# UnoMuxShieldV1_0.net
KiCad netlist of a schematic drawn in EAGLE
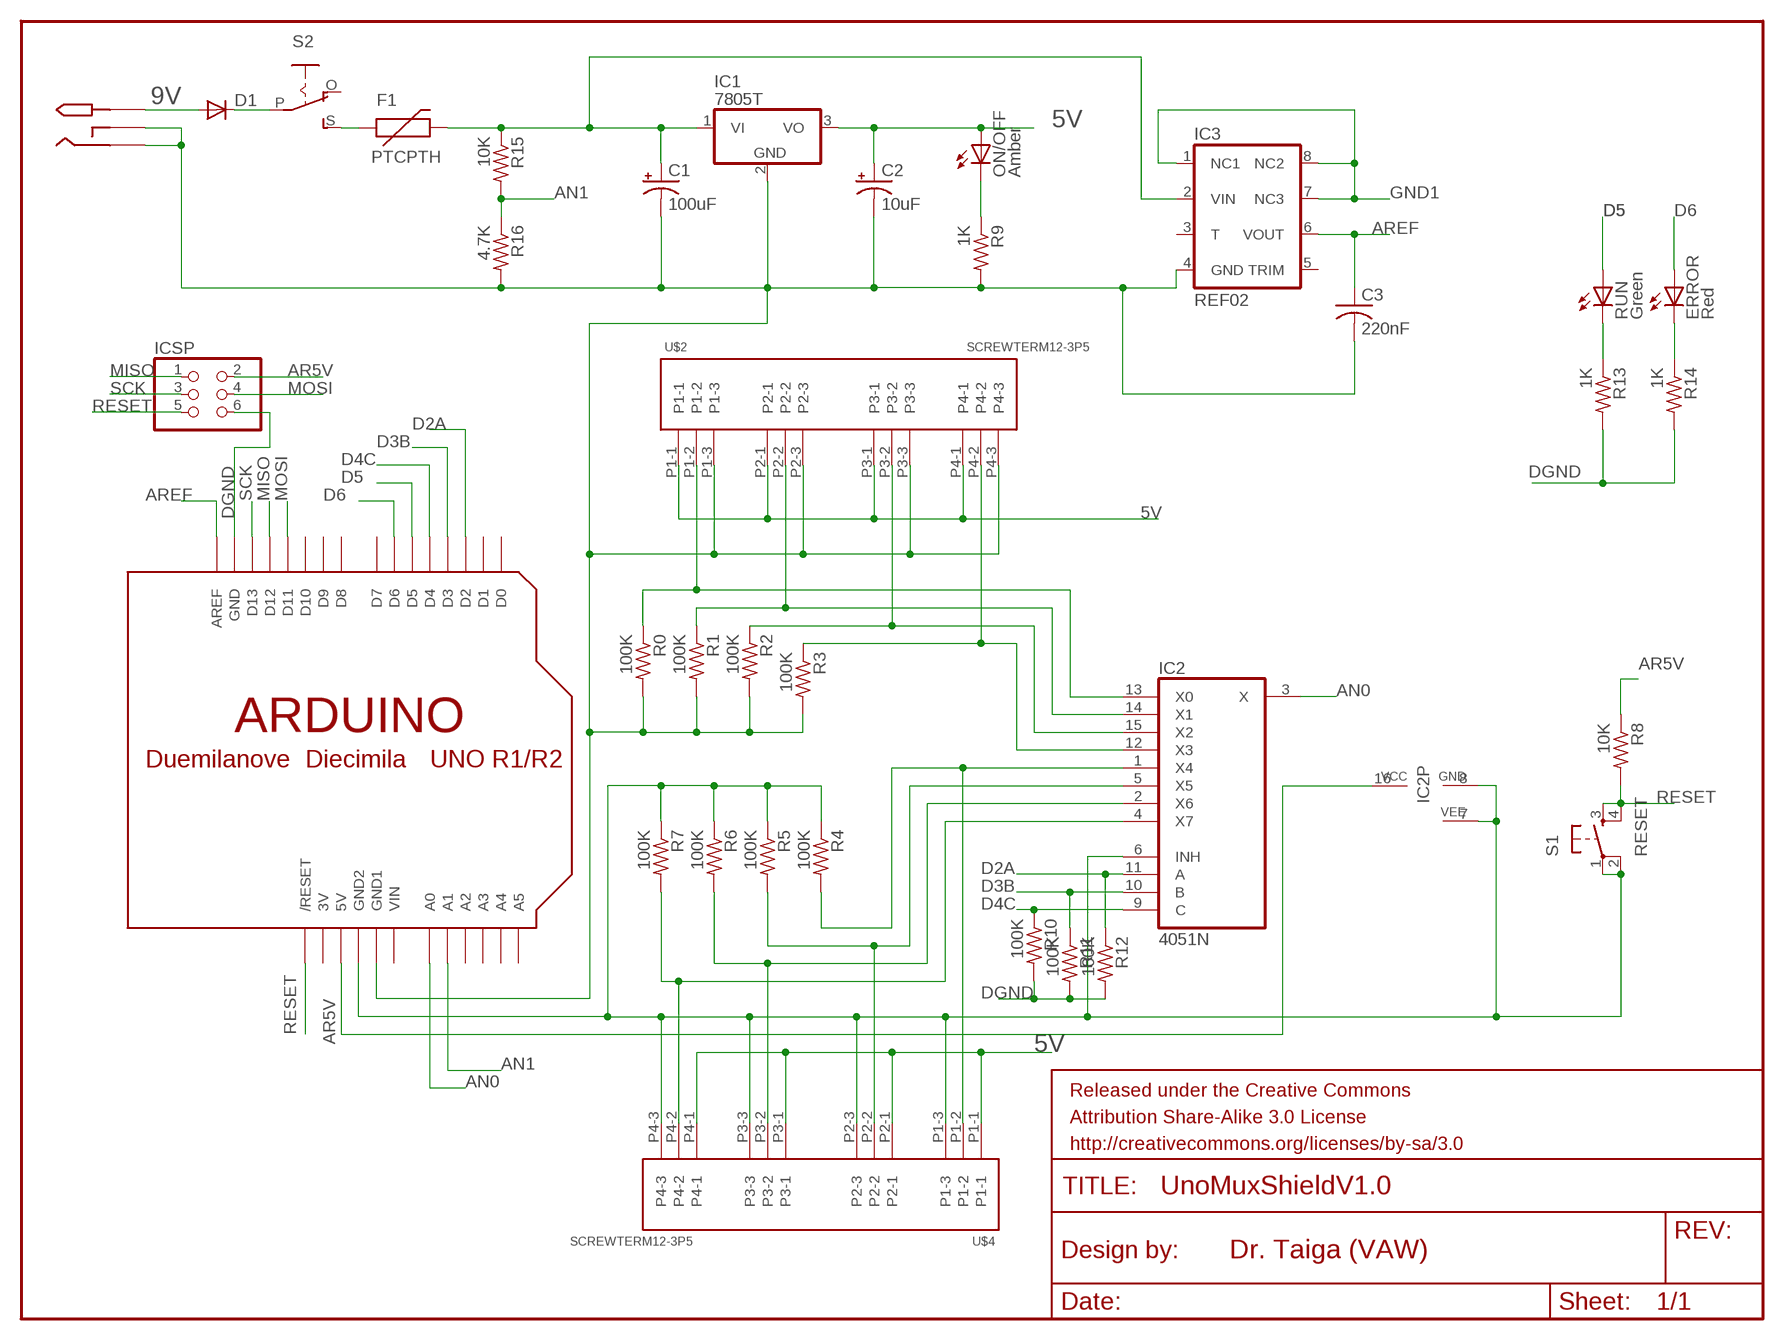
[diagram p0: schematic, sheet 1]

(export (version "E")
  (design (tool "Eeschema 10.0.6"))
  (components
    (comp (ref "C1")
      (value "100uF")
      (footprint "eagle-import:E2,5-6E")
      (libsource (lib "eagle-import") (part "CPOL-USE2,5-6E"))
    )
    (comp (ref "C2")
      (value "10uF")
      (footprint "eagle-import:E1,8-4")
      (libsource (lib "eagle-import") (part "CPOL-USE1.8-4"))
    )
    (comp (ref "C3")
      (value "220nF")
      (footprint "eagle-import:C050-024X044")
      (libsource (lib "eagle-import") (part "C-US050-024X044"))
    )
    (comp (ref "D1")
      (value "DIODEPTH")
      (footprint "eagle-import:DIODE-1N4001")
      (libsource (lib "eagle-import") (part "DIODEPTH"))
    )
    (comp (ref "ERROR")
      (value "Red")
      (footprint "eagle-import:LED3MM")
      (libsource (lib "eagle-import") (part "LED3MM"))
    )
    (comp (ref "F1")
      (value "PTCPTH")
      (footprint "eagle-import:PTC")
      (libsource (lib "eagle-import") (part "PTCPTH"))
    )
    (comp (ref "IC1")
      (value "7805T")
      (footprint "eagle-import:TO220H")
      (libsource (lib "eagle-import") (part "78T05"))
    )
    (comp (ref "IC2")
      (value "4051N")
      (footprint "eagle-import:DIL16")
      (libsource (lib "eagle-import") (part "4051N"))
    )
    (comp (ref "IC3")
      (value "REF02")
      (footprint "eagle-import:DIL08")
      (libsource (lib "eagle-import") (part "REF02"))
    )
    (comp (ref "ICSP")
      (value "PINHD-2X3")
      (footprint "eagle-import:2X03")
      (libsource (lib "eagle-import") (part "PINHD-2X3"))
    )
    (comp (ref "ON/OFF")
      (value "Amber")
      (footprint "eagle-import:LED3MM")
      (libsource (lib "eagle-import") (part "LED3MM"))
    )
    (comp (ref "R0")
      (value "100K")
      (footprint "eagle-import:0207_10")
      (libsource (lib "eagle-import") (part "R-US_0207/10"))
    )
    (comp (ref "R1")
      (value "100K")
      (footprint "eagle-import:0207_10")
      (libsource (lib "eagle-import") (part "R-US_0207/10"))
    )
    (comp (ref "R2")
      (value "100K")
      (footprint "eagle-import:0207_10")
      (libsource (lib "eagle-import") (part "R-US_0207/10"))
    )
    (comp (ref "R3")
      (value "100K")
      (footprint "eagle-import:0207_10")
      (libsource (lib "eagle-import") (part "R-US_0207/10"))
    )
    (comp (ref "R4")
      (value "100K")
      (footprint "eagle-import:0207_10")
      (libsource (lib "eagle-import") (part "R-US_0207/10"))
    )
    (comp (ref "R5")
      (value "100K")
      (footprint "eagle-import:0207_10")
      (libsource (lib "eagle-import") (part "R-US_0207/10"))
    )
    (comp (ref "R6")
      (value "100K")
      (footprint "eagle-import:0207_10")
      (libsource (lib "eagle-import") (part "R-US_0207/10"))
    )
    (comp (ref "R7")
      (value "100K")
      (footprint "eagle-import:0207_10")
      (libsource (lib "eagle-import") (part "R-US_0207/10"))
    )
    (comp (ref "R8")
      (value "10K")
      (footprint "eagle-import:0207_10")
      (libsource (lib "eagle-import") (part "R-US_0207/10"))
    )
    (comp (ref "R9")
      (value "1K")
      (footprint "eagle-import:0207_10")
      (libsource (lib "eagle-import") (part "R-US_0207/10"))
    )
    (comp (ref "R10")
      (value "100K")
      (footprint "eagle-import:0207_10")
      (libsource (lib "eagle-import") (part "R-US_0207/10"))
    )
    (comp (ref "R11")
      (value "100K")
      (footprint "eagle-import:0207_10")
      (libsource (lib "eagle-import") (part "R-US_0207/10"))
    )
    (comp (ref "R12")
      (value "100K")
      (footprint "eagle-import:0207_10")
      (libsource (lib "eagle-import") (part "R-US_0207/10"))
    )
    (comp (ref "R13")
      (value "1K")
      (footprint "eagle-import:0207_10")
      (libsource (lib "eagle-import") (part "R-US_0207/10"))
    )
    (comp (ref "R14")
      (value "1K")
      (footprint "eagle-import:0207_10")
      (libsource (lib "eagle-import") (part "R-US_0207/10"))
    )
    (comp (ref "R15")
      (value "10K")
      (footprint "eagle-import:0207_10")
      (libsource (lib "eagle-import") (part "R-US_0207/10"))
    )
    (comp (ref "R16")
      (value "4.7K")
      (footprint "eagle-import:0207_10")
      (libsource (lib "eagle-import") (part "R-US_0207/10"))
    )
    (comp (ref "RUN")
      (value "Green")
      (footprint "eagle-import:LED3MM")
      (libsource (lib "eagle-import") (part "LED3MM"))
    )
    (comp (ref "S1")
      (value "RESET")
      (footprint "eagle-import:TACTILE-PTH")
      (libsource (lib "eagle-import") (part "TAC_SWITCHPTH"))
    )
    (comp (ref "S2")
      (value "EG1218S")
      (footprint "eagle-import:EG1218")
      (libsource (lib "eagle-import") (part "EG1218S"))
    )
    (comp (ref "U$1")
      (value "ARDUINO-NOHOLE")
      (footprint "eagle-import:ARDUINO-NOHOLE")
      (libsource (lib "eagle-import") (part "ARDUINO-NOHOLE"))
    )
    (comp (ref "U$2")
      (value "SCREWTERM12-3P5")
      (footprint "eagle-import:SCREWTERM3P5")
      (libsource (lib "eagle-import") (part "SCREWTERM12-3P5"))
    )
    (comp (ref "U$4")
      (value "SCREWTERM12-3P5")
      (footprint "eagle-import:SCREWTERM3P5")
      (libsource (lib "eagle-import") (part "SCREWTERM12-3P5"))
    )
    (comp (ref "U$5")
      (value "PJ-102-A")
      (footprint "eagle-import:PJ-102-A")
      (libsource (lib "eagle-import") (part "PJ-102-A"))
    )
  )
  (nets
    (net (code "1") (name "/3V") (class "Default")
      (node (ref "U$1") (pin "3V") (pinfunction "3V_3V") (pintype "power_in"))
    )
    (net (code "2") (name "/5V") (class "Default")
      (node (ref "C2") (pin "+") (pinfunction "+_+") (pintype "passive"))
      (node (ref "IC1") (pin "3") (pinfunction "VO_3") (pintype "passive"))
      (node (ref "ON/OFF") (pin "A") (pinfunction "A_A") (pintype "passive"))
      (node (ref "U$2") (pin "P1-1") (pinfunction "P1-1_P1-1") (pintype "bidirectional"))
      (node (ref "U$2") (pin "P2-1") (pinfunction "P2-1_P2-1") (pintype "bidirectional"))
      (node (ref "U$2") (pin "P3-1") (pinfunction "P3-1_P3-1") (pintype "bidirectional"))
      (node (ref "U$2") (pin "P4-1") (pinfunction "P4-1_P4-1") (pintype "bidirectional"))
      (node (ref "U$4") (pin "P1-1") (pinfunction "P1-1_P1-1") (pintype "bidirectional"))
      (node (ref "U$4") (pin "P2-1") (pinfunction "P2-1_P2-1") (pintype "bidirectional"))
      (node (ref "U$4") (pin "P3-1") (pinfunction "P3-1_P3-1") (pintype "bidirectional"))
      (node (ref "U$4") (pin "P4-1") (pinfunction "P4-1_P4-1") (pintype "bidirectional"))
    )
    (net (code "3") (name "/9V") (class "Default")
      (node (ref "D1") (pin "A") (pinfunction "A_A") (pintype "passive"))
      (node (ref "U$5") (pin "P$1_TIP") (pinfunction "TIP_P$1_TIP") (pintype "bidirectional"))
    )
    (net (code "4") (name "/AN0") (class "Default")
      (node (ref "IC2") (pin "3") (pinfunction "X_3") (pintype "bidirectional"))
      (node (ref "U$1") (pin "A0") (pinfunction "A0_A0") (pintype "bidirectional"))
    )
    (net (code "5") (name "/AN1") (class "Default")
      (node (ref "R15") (pin "2") (pinfunction "2_2") (pintype "passive"))
      (node (ref "R16") (pin "1") (pinfunction "1_1") (pintype "passive"))
      (node (ref "U$1") (pin "A1") (pinfunction "A1_A1") (pintype "bidirectional"))
    )
    (net (code "6") (name "/AR5V") (class "Default")
      (node (ref "IC2") (pin "16") (pinfunction "VCC_16") (pintype "power_in"))
      (node (ref "ICSP") (pin "2") (pinfunction "2_2") (pintype "passive"))
      (node (ref "R8") (pin "1") (pinfunction "1_1") (pintype "passive"))
      (node (ref "U$1") (pin "5V") (pinfunction "5V_5V") (pintype "power_in"))
    )
    (net (code "7") (name "/AREF") (class "Default")
      (node (ref "C3") (pin "1") (pinfunction "1_1") (pintype "passive"))
      (node (ref "IC3") (pin "6") (pinfunction "VOUT_6") (pintype "input"))
      (node (ref "U$1") (pin "AREF") (pinfunction "AREF_AREF") (pintype "bidirectional"))
    )
    (net (code "8") (name "/D2A") (class "Default")
      (node (ref "IC2") (pin "11") (pinfunction "A_11") (pintype "input"))
      (node (ref "R12") (pin "1") (pinfunction "1_1") (pintype "passive"))
      (node (ref "U$1") (pin "D2") (pinfunction "D2_D2") (pintype "bidirectional"))
    )
    (net (code "9") (name "/D3B") (class "Default")
      (node (ref "IC2") (pin "10") (pinfunction "B_10") (pintype "input"))
      (node (ref "R11") (pin "1") (pinfunction "1_1") (pintype "passive"))
      (node (ref "U$1") (pin "D3") (pinfunction "D3_D3") (pintype "bidirectional"))
    )
    (net (code "10") (name "/D4C") (class "Default")
      (node (ref "IC2") (pin "9") (pinfunction "C_9") (pintype "input"))
      (node (ref "R10") (pin "1") (pinfunction "1_1") (pintype "passive"))
      (node (ref "U$1") (pin "D4") (pinfunction "D4_D4") (pintype "bidirectional"))
    )
    (net (code "11") (name "/D5") (class "Default")
      (node (ref "RUN") (pin "A") (pinfunction "A_A") (pintype "passive"))
      (node (ref "U$1") (pin "D5") (pinfunction "D5_D5") (pintype "bidirectional"))
    )
    (net (code "12") (name "/D6") (class "Default")
      (node (ref "ERROR") (pin "A") (pinfunction "A_A") (pintype "passive"))
      (node (ref "U$1") (pin "D6") (pinfunction "D6_D6") (pintype "bidirectional"))
    )
    (net (code "13") (name "/DGND") (class "Default")
      (node (ref "ICSP") (pin "6") (pinfunction "6_6") (pintype "passive"))
      (node (ref "R10") (pin "2") (pinfunction "2_2") (pintype "passive"))
      (node (ref "R11") (pin "2") (pinfunction "2_2") (pintype "passive"))
      (node (ref "R12") (pin "2") (pinfunction "2_2") (pintype "passive"))
      (node (ref "R13") (pin "2") (pinfunction "2_2") (pintype "passive"))
      (node (ref "R14") (pin "2") (pinfunction "2_2") (pintype "passive"))
      (node (ref "U$1") (pin "GND") (pinfunction "GND_GND") (pintype "power_in"))
    )
    (net (code "14") (name "/GND1") (class "Default")
      (node (ref "IC3") (pin "1") (pinfunction "NC1_1") (pintype "input"))
      (node (ref "IC3") (pin "7") (pinfunction "NC3_7") (pintype "input"))
      (node (ref "IC3") (pin "8") (pinfunction "NC2_8") (pintype "output"))
    )
    (net (code "15") (name "/MISO") (class "Default")
      (node (ref "ICSP") (pin "1") (pinfunction "1_1") (pintype "passive"))
      (node (ref "U$1") (pin "D12") (pinfunction "D12_D12") (pintype "bidirectional"))
    )
    (net (code "16") (name "/MOSI") (class "Default")
      (node (ref "ICSP") (pin "4") (pinfunction "4_4") (pintype "passive"))
      (node (ref "U$1") (pin "D11") (pinfunction "D11_D11") (pintype "bidirectional"))
    )
    (net (code "17") (name "/RESET") (class "Default")
      (node (ref "ICSP") (pin "5") (pinfunction "5_5") (pintype "passive"))
      (node (ref "R8") (pin "2") (pinfunction "2_2") (pintype "passive"))
      (node (ref "S1") (pin "3") (pinfunction "3_3") (pintype "passive"))
      (node (ref "S1") (pin "4") (pinfunction "4_4") (pintype "passive"))
      (node (ref "U$1") (pin "RESET") (pinfunction "/RESET_RESET") (pintype "bidirectional"))
    )
    (net (code "18") (name "/SCK") (class "Default")
      (node (ref "ICSP") (pin "3") (pinfunction "3_3") (pintype "passive"))
      (node (ref "U$1") (pin "D13") (pinfunction "D13_D13") (pintype "bidirectional"))
    )
    (net (code "19") (name "/TRIM") (class "Default")
      (node (ref "IC3") (pin "5") (pinfunction "TRIM_5") (pintype "power_in"))
    )
    (net (code "20") (name "/VIN") (class "Default")
      (node (ref "U$1") (pin "VIN") (pinfunction "VIN_VIN") (pintype "power_in"))
    )
    (net (code "21") (name "Net-(D1-PadC)") (class "Default")
      (node (ref "D1") (pin "C") (pinfunction "C_C") (pintype "passive"))
      (node (ref "S2") (pin "P") (pinfunction "P_P") (pintype "passive"))
    )
    (net (code "22") (name "Net-(ERROR-C)") (class "Default")
      (node (ref "ERROR") (pin "K") (pinfunction "C_K") (pintype "passive"))
      (node (ref "R14") (pin "1") (pinfunction "1_1") (pintype "passive"))
    )
    (net (code "23") (name "Net-(F1-1)") (class "Default")
      (node (ref "F1") (pin "P$1") (pinfunction "1_P$1") (pintype "bidirectional"))
      (node (ref "S2") (pin "S") (pinfunction "S_S") (pintype "passive"))
    )
    (net (code "24") (name "Net-(F1-2)") (class "Default")
      (node (ref "C1") (pin "+") (pinfunction "+_+") (pintype "passive"))
      (node (ref "F1") (pin "P$2") (pinfunction "2_P$2") (pintype "bidirectional"))
      (node (ref "IC1") (pin "1") (pinfunction "VI_1") (pintype "input"))
      (node (ref "IC3") (pin "2") (pinfunction "VIN_2") (pintype "bidirectional"))
      (node (ref "R15") (pin "1") (pinfunction "1_1") (pintype "passive"))
    )
    (net (code "25") (name "Net-(IC1-GND)") (class "Default")
      (node (ref "C1") (pin "-") (pinfunction "-_-") (pintype "passive"))
      (node (ref "C2") (pin "-") (pinfunction "-_-") (pintype "passive"))
      (node (ref "C3") (pin "2") (pinfunction "2_2") (pintype "passive"))
      (node (ref "IC1") (pin "2") (pinfunction "GND_2") (pintype "passive"))
      (node (ref "IC3") (pin "4") (pinfunction "GND_4") (pintype "power_in"))
      (node (ref "R0") (pin "2") (pinfunction "2_2") (pintype "passive"))
      (node (ref "R1") (pin "2") (pinfunction "2_2") (pintype "passive"))
      (node (ref "R16") (pin "2") (pinfunction "2_2") (pintype "passive"))
      (node (ref "R2") (pin "2") (pinfunction "2_2") (pintype "passive"))
      (node (ref "R3") (pin "2") (pinfunction "2_2") (pintype "passive"))
      (node (ref "R9") (pin "2") (pinfunction "2_2") (pintype "passive"))
      (node (ref "U$1") (pin "GND1") (pinfunction "GND1_GND1") (pintype "power_in"))
      (node (ref "U$2") (pin "P1-3") (pinfunction "P1-3_P1-3") (pintype "bidirectional"))
      (node (ref "U$2") (pin "P2-3") (pinfunction "P2-3_P2-3") (pintype "bidirectional"))
      (node (ref "U$2") (pin "P3-3") (pinfunction "P3-3_P3-3") (pintype "bidirectional"))
      (node (ref "U$2") (pin "P4-3") (pinfunction "P4-3_P4-3") (pintype "bidirectional"))
      (node (ref "U$5") (pin "P$2_SLEEVE") (pinfunction "SLEEVE_P$2_SLEEVE") (pintype "bidirectional"))
      (node (ref "U$5") (pin "P$3_SHUNT") (pinfunction "SHUNT_P$3_SHUNT") (pintype "bidirectional"))
    )
    (net (code "26") (name "Net-(IC2A-INH)") (class "Default")
      (node (ref "IC2") (pin "6") (pinfunction "INH_6") (pintype "input"))
      (node (ref "IC2") (pin "7") (pinfunction "VEE_7") (pintype "power_in"))
      (node (ref "IC2") (pin "8") (pinfunction "GND_8") (pintype "power_in"))
      (node (ref "R4") (pin "1") (pinfunction "1_1") (pintype "passive"))
      (node (ref "R5") (pin "1") (pinfunction "1_1") (pintype "passive"))
      (node (ref "R6") (pin "1") (pinfunction "1_1") (pintype "passive"))
      (node (ref "R7") (pin "1") (pinfunction "1_1") (pintype "passive"))
      (node (ref "S1") (pin "1") (pinfunction "1_1") (pintype "passive"))
      (node (ref "S1") (pin "2") (pinfunction "2_2") (pintype "passive"))
      (node (ref "U$1") (pin "GND2") (pinfunction "GND2_GND2") (pintype "power_in"))
      (node (ref "U$4") (pin "P1-3") (pinfunction "P1-3_P1-3") (pintype "bidirectional"))
      (node (ref "U$4") (pin "P2-3") (pinfunction "P2-3_P2-3") (pintype "bidirectional"))
      (node (ref "U$4") (pin "P3-3") (pinfunction "P3-3_P3-3") (pintype "bidirectional"))
      (node (ref "U$4") (pin "P4-3") (pinfunction "P4-3_P4-3") (pintype "bidirectional"))
    )
    (net (code "27") (name "Net-(IC2A-X0)") (class "Default")
      (node (ref "IC2") (pin "13") (pinfunction "X0_13") (pintype "bidirectional"))
      (node (ref "R0") (pin "1") (pinfunction "1_1") (pintype "passive"))
      (node (ref "U$2") (pin "P1-2") (pinfunction "P1-2_P1-2") (pintype "bidirectional"))
    )
    (net (code "28") (name "Net-(IC2A-X1)") (class "Default")
      (node (ref "IC2") (pin "14") (pinfunction "X1_14") (pintype "bidirectional"))
      (node (ref "R1") (pin "1") (pinfunction "1_1") (pintype "passive"))
      (node (ref "U$2") (pin "P2-2") (pinfunction "P2-2_P2-2") (pintype "bidirectional"))
    )
    (net (code "29") (name "Net-(IC2A-X2)") (class "Default")
      (node (ref "IC2") (pin "15") (pinfunction "X2_15") (pintype "bidirectional"))
      (node (ref "R2") (pin "1") (pinfunction "1_1") (pintype "passive"))
      (node (ref "U$2") (pin "P3-2") (pinfunction "P3-2_P3-2") (pintype "bidirectional"))
    )
    (net (code "30") (name "Net-(IC2A-X3)") (class "Default")
      (node (ref "IC2") (pin "12") (pinfunction "X3_12") (pintype "bidirectional"))
      (node (ref "R3") (pin "1") (pinfunction "1_1") (pintype "passive"))
      (node (ref "U$2") (pin "P4-2") (pinfunction "P4-2_P4-2") (pintype "bidirectional"))
    )
    (net (code "31") (name "Net-(IC2A-X4)") (class "Default")
      (node (ref "IC2") (pin "1") (pinfunction "X4_1") (pintype "bidirectional"))
      (node (ref "R4") (pin "2") (pinfunction "2_2") (pintype "passive"))
      (node (ref "U$4") (pin "P1-2") (pinfunction "P1-2_P1-2") (pintype "bidirectional"))
    )
    (net (code "32") (name "Net-(IC2A-X5)") (class "Default")
      (node (ref "IC2") (pin "5") (pinfunction "X5_5") (pintype "bidirectional"))
      (node (ref "R5") (pin "2") (pinfunction "2_2") (pintype "passive"))
      (node (ref "U$4") (pin "P2-2") (pinfunction "P2-2_P2-2") (pintype "bidirectional"))
    )
    (net (code "33") (name "Net-(IC2A-X6)") (class "Default")
      (node (ref "IC2") (pin "2") (pinfunction "X6_2") (pintype "bidirectional"))
      (node (ref "R6") (pin "2") (pinfunction "2_2") (pintype "passive"))
      (node (ref "U$4") (pin "P3-2") (pinfunction "P3-2_P3-2") (pintype "bidirectional"))
    )
    (net (code "34") (name "Net-(IC2A-X7)") (class "Default")
      (node (ref "IC2") (pin "4") (pinfunction "X7_4") (pintype "bidirectional"))
      (node (ref "R7") (pin "2") (pinfunction "2_2") (pintype "passive"))
      (node (ref "U$4") (pin "P4-2") (pinfunction "P4-2_P4-2") (pintype "bidirectional"))
    )
    (net (code "35") (name "Net-(ON/OFF-C)") (class "Default")
      (node (ref "ON/OFF") (pin "K") (pinfunction "C_K") (pintype "passive"))
      (node (ref "R9") (pin "1") (pinfunction "1_1") (pintype "passive"))
    )
    (net (code "36") (name "Net-(RUN-C)") (class "Default")
      (node (ref "R13") (pin "1") (pinfunction "1_1") (pintype "passive"))
      (node (ref "RUN") (pin "K") (pinfunction "C_K") (pintype "passive"))
    )
    (net (code "37") (name "unconnected-(IC3-T-Pad3)") (class "Default")
      (node (ref "IC3") (pin "3") (pinfunction "T_3") (pintype "input"))
    )
    (net (code "38") (name "unconnected-(S2-PadO)") (class "Default")
      (node (ref "S2") (pin "O") (pinfunction "O_O") (pintype "passive"))
    )
    (net (code "39") (name "unconnected-(U$1-PadA2)") (class "Default")
      (node (ref "U$1") (pin "A2") (pinfunction "A2_A2") (pintype "bidirectional"))
    )
    (net (code "40") (name "unconnected-(U$1-PadA3)") (class "Default")
      (node (ref "U$1") (pin "A3") (pinfunction "A3_A3") (pintype "bidirectional"))
    )
    (net (code "41") (name "unconnected-(U$1-PadA4)") (class "Default")
      (node (ref "U$1") (pin "A4") (pinfunction "A4_A4") (pintype "bidirectional"))
    )
    (net (code "42") (name "unconnected-(U$1-PadA5)") (class "Default")
      (node (ref "U$1") (pin "A5") (pinfunction "A5_A5") (pintype "bidirectional"))
    )
    (net (code "43") (name "unconnected-(U$1-PadD0)") (class "Default")
      (node (ref "U$1") (pin "D0") (pinfunction "D0_D0") (pintype "bidirectional"))
    )
    (net (code "44") (name "unconnected-(U$1-PadD1)") (class "Default")
      (node (ref "U$1") (pin "D1") (pinfunction "D1_D1") (pintype "bidirectional"))
    )
    (net (code "45") (name "unconnected-(U$1-PadD7)") (class "Default")
      (node (ref "U$1") (pin "D7") (pinfunction "D7_D7") (pintype "bidirectional"))
    )
    (net (code "46") (name "unconnected-(U$1-PadD8)") (class "Default")
      (node (ref "U$1") (pin "D8") (pinfunction "D8_D8") (pintype "bidirectional"))
    )
    (net (code "47") (name "unconnected-(U$1-PadD9)") (class "Default")
      (node (ref "U$1") (pin "D9") (pinfunction "D9_D9") (pintype "bidirectional"))
    )
    (net (code "48") (name "unconnected-(U$1-PadD10)") (class "Default")
      (node (ref "U$1") (pin "D10") (pinfunction "D10_D10") (pintype "bidirectional"))
    )
  )
)
